# Encoder.net
KiCad netlist of a schematic drawn in Altium Designer
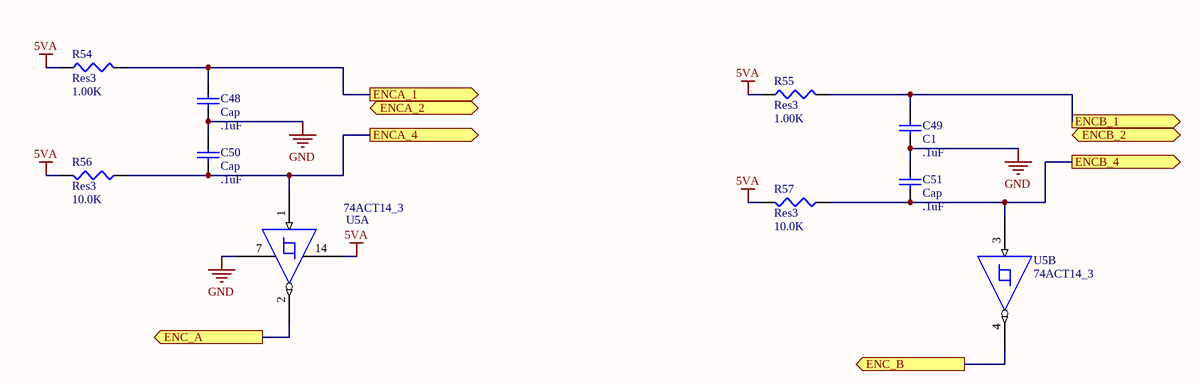
[diagram p0: Encoder.SchDoc]

(export (version "E")
  (design (tool "Eeschema 10.0.6"))
  (components
    (comp (ref "C48")
      (value "Cap")
      (footprint "CAPC2012X09M")
      (description "CAP CER .1uF 16v X7R 0805")
      (fields (field (name "ALTIUM_VALUE") ".1uF") (field (name "MPN") "C0805C104K4RACTU"))
      (libsource (lib "esd_library") (part "CAP-X7R-.1uF-16V-±10%"))
    )
    (comp (ref "C49")
      (value "C1")
      (footprint "CAPC2012X09M")
      (description "CAP CER .1uF 16v X7R 0805")
      (fields (field (name "ALTIUM_VALUE") ".1uF") (field (name "MPN") "C0805C104K4RACTU"))
      (libsource (lib "esd_library") (part "CAP-X7R-.1uF-16V-±10%"))
    )
    (comp (ref "C50")
      (value "Cap")
      (footprint "CAPC2012X09M")
      (description "CAP CER .1uF 16v X7R 0805")
      (fields (field (name "ALTIUM_VALUE") ".1uF") (field (name "MPN") "C0805C104K4RACTU"))
      (libsource (lib "esd_library") (part "CAP-X7R-.1uF-16V-±10%"))
    )
    (comp (ref "C51")
      (value "Cap")
      (footprint "CAPC2012X09M")
      (description "CAP CER .1uF 16v X7R 0805")
      (fields (field (name "ALTIUM_VALUE") ".1uF") (field (name "MPN") "C0805C104K4RACTU"))
      (libsource (lib "esd_library") (part "CAP-X7R-.1uF-16V-±10%"))
    )
    (comp (ref "R54")
      (value "Res3")
      (footprint "RESC2112X05M")
      (description "RES SMD 1.00K OHM 1% 1/8W 0805")
      (fields (field (name "ALTIUM_VALUE") "1.00K") (field (name "MPN") "CRCW08051K00FKEA"))
      (libsource (lib "esd_library (1)") (part "Resistor_1.00K"))
    )
    (comp (ref "R55")
      (value "Res3")
      (footprint "RESC2112X05M")
      (description "RES SMD 1.00K OHM 1% 1/8W 0805")
      (fields (field (name "ALTIUM_VALUE") "1.00K") (field (name "MPN") "CRCW08051K00FKEA"))
      (libsource (lib "esd_library (1)") (part "Resistor_1.00K"))
    )
    (comp (ref "R56")
      (value "Res3")
      (footprint "RESC2112X05M")
      (description "RES SMD 10.0K OHM 1% 1/8W 0805")
      (fields (field (name "ALTIUM_VALUE") "10.0K") (field (name "MPN") "CRCW080510K0FKEA"))
      (libsource (lib "esd_library") (part "Resistor_10.0K"))
    )
    (comp (ref "R57")
      (value "Res3")
      (footprint "RESC2112X05M")
      (description "RES SMD 10.0K OHM 1% 1/8W 0805")
      (fields (field (name "ALTIUM_VALUE") "10.0K") (field (name "MPN") "CRCW080510K0FKEA"))
      (libsource (lib "esd_library") (part "Resistor_10.0K"))
    )
    (comp (ref "U5")
      (value "74ACT14_3")
      (footprint "SOIC127P600X175-14M")
      (description "IC INVERTER HEX SCHMITT 14SOIC")
      (fields (field (name "MPN") "74ACT14SCX"))
      (libsource (lib "esd_library") (part "74ACT14_3"))
    )
  )
  (nets
    (net (code "1") (name "/ENCA_1") (class "Default")
      (node (ref "C48") (pin "2") (pinfunction "2_2") (pintype "passive"))
      (node (ref "R54") (pin "2") (pinfunction "2_2") (pintype "passive"))
    )
    (net (code "3") (name "/ENCA_4") (class "Default")
      (node (ref "C50") (pin "1") (pinfunction "1_1") (pintype "passive"))
      (node (ref "R56") (pin "1") (pinfunction "1_1") (pintype "passive"))
      (node (ref "U5") (pin "1") (pinfunction "A_1") (pintype "input"))
    )
    (net (code "4") (name "/ENCB_1") (class "Default")
      (node (ref "C49") (pin "2") (pinfunction "2_2") (pintype "passive"))
      (node (ref "R55") (pin "2") (pinfunction "2_2") (pintype "passive"))
    )
    (net (code "6") (name "/ENCB_4") (class "Default")
      (node (ref "C51") (pin "1") (pinfunction "1_1") (pintype "passive"))
      (node (ref "R57") (pin "1") (pinfunction "1_1") (pintype "passive"))
      (node (ref "U5") (pin "3") (pinfunction "A_3") (pintype "input"))
    )
    (net (code "7") (name "/ENC_A") (class "Default")
      (node (ref "U5") (pin "2") (pinfunction "Y_2") (pintype "output"))
    )
    (net (code "8") (name "/ENC_B") (class "Default")
      (node (ref "U5") (pin "4") (pinfunction "Y_4") (pintype "output"))
    )
    (net (code "9") (name "5VA") (class "Default")
      (node (ref "R54") (pin "1") (pinfunction "1_1") (pintype "passive"))
      (node (ref "R55") (pin "1") (pinfunction "1_1") (pintype "passive"))
      (node (ref "R56") (pin "2") (pinfunction "2_2") (pintype "passive"))
      (node (ref "R57") (pin "2") (pinfunction "2_2") (pintype "passive"))
      (node (ref "U5") (pin "14") (pinfunction "VCC_14") (pintype "power_in"))
    )
    (net (code "10") (name "GND") (class "Default")
      (node (ref "C48") (pin "1") (pinfunction "1_1") (pintype "passive"))
      (node (ref "C49") (pin "1") (pinfunction "1_1") (pintype "passive"))
      (node (ref "C50") (pin "2") (pinfunction "2_2") (pintype "passive"))
      (node (ref "C51") (pin "2") (pinfunction "2_2") (pintype "passive"))
      (node (ref "U5") (pin "7") (pinfunction "GND_POWER_7") (pintype "power_in"))
    )
  )
)
